# double-dice.net
KiCad netlist of a schematic drawn in EAGLE
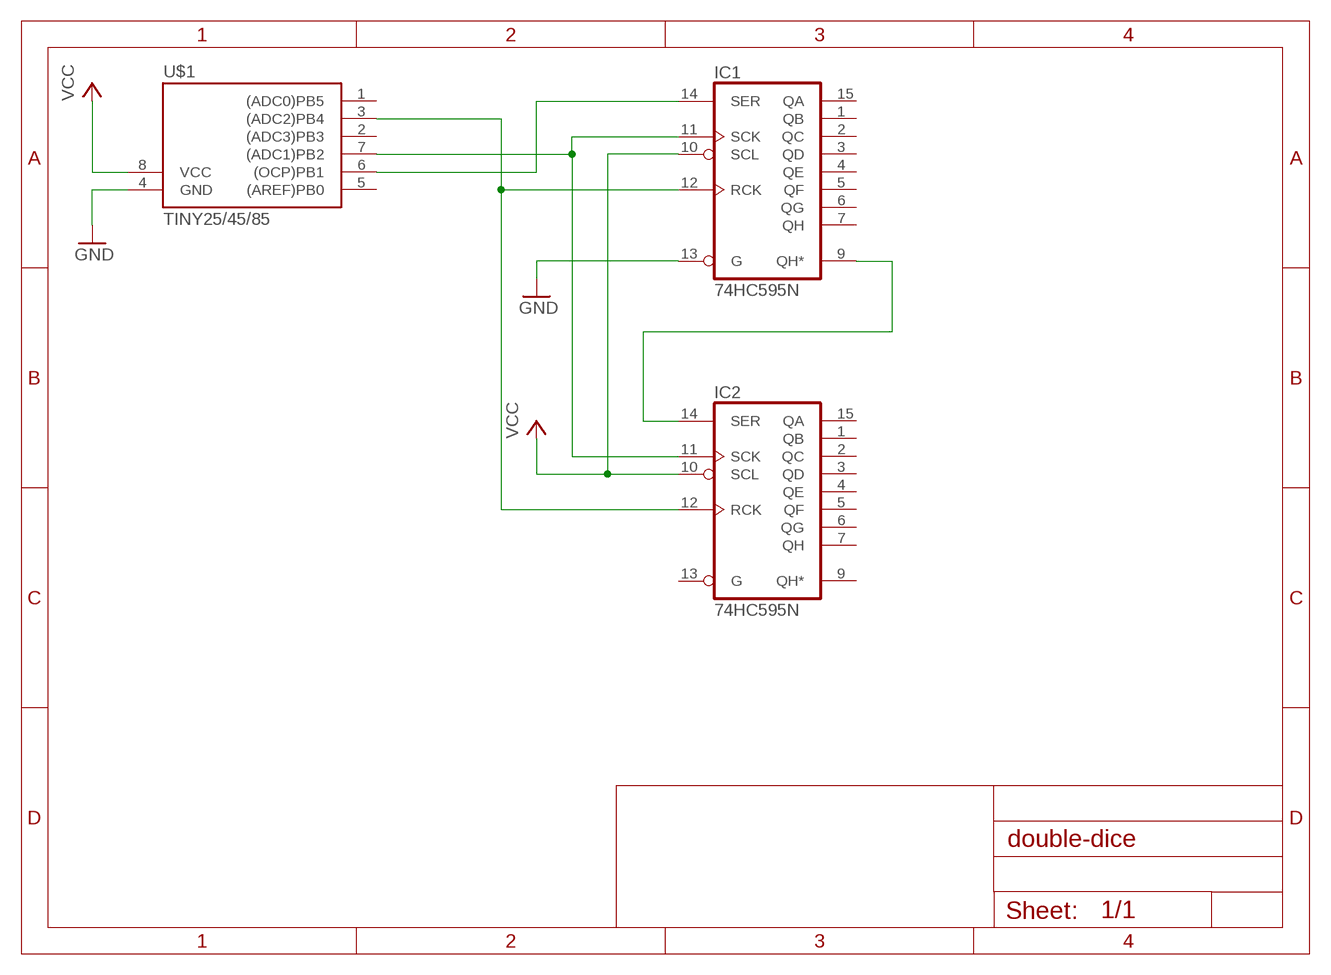
[diagram p0: schematic, sheet 1]

(export (version "E")
  (design (tool "Eeschema 10.0.6"))
  (components
    (comp (ref "IC1")
      (value "74HC595N")
      (footprint "eagle-import:DIL16")
      (libsource (lib "eagle-import") (part "74595NHC"))
    )
    (comp (ref "IC2")
      (value "74HC595N")
      (footprint "eagle-import:DIL16")
      (libsource (lib "eagle-import") (part "74595NHC"))
    )
    (comp (ref "U$1")
      (value "TINY25/45/85")
      (footprint "eagle-import:DIL08")
      (libsource (lib "eagle-import") (part "TINY25/45/85"))
    )
  )
  (nets
    (net (code "1") (name "GND") (class "Default")
      (node (ref "IC1") (pin "13") (pinfunction "G_13") (pintype "input"))
      (node (ref "U$1") (pin "4") (pinfunction "GND_4") (pintype "power_in"))
    )
    (net (code "2") (name "Net-(IC1A-QH*)") (class "Default")
      (node (ref "IC1") (pin "9") (pinfunction "QH*_9") (pintype "tri_state"))
      (node (ref "IC2") (pin "14") (pinfunction "SER_14") (pintype "input"))
    )
    (net (code "3") (name "Net-(IC1A-RCK)") (class "Default")
      (node (ref "IC1") (pin "12") (pinfunction "RCK_12") (pintype "input"))
      (node (ref "IC2") (pin "12") (pinfunction "RCK_12") (pintype "input"))
      (node (ref "U$1") (pin "3") (pinfunction "(ADC2)PB4_3") (pintype "bidirectional"))
    )
    (net (code "4") (name "Net-(IC1A-SCK)") (class "Default")
      (node (ref "IC1") (pin "11") (pinfunction "SCK_11") (pintype "input"))
      (node (ref "IC2") (pin "11") (pinfunction "SCK_11") (pintype "input"))
      (node (ref "U$1") (pin "7") (pinfunction "(ADC1)PB2_7") (pintype "bidirectional"))
    )
    (net (code "5") (name "Net-(IC1A-SER)") (class "Default")
      (node (ref "IC1") (pin "14") (pinfunction "SER_14") (pintype "input"))
      (node (ref "U$1") (pin "6") (pinfunction "(OCP)PB1_6") (pintype "bidirectional"))
    )
    (net (code "6") (name "VCC") (class "Default")
      (node (ref "IC1") (pin "10") (pinfunction "SCL_10") (pintype "input"))
      (node (ref "IC2") (pin "10") (pinfunction "SCL_10") (pintype "input"))
      (node (ref "U$1") (pin "8") (pinfunction "VCC_8") (pintype "power_in"))
    )
    (net (code "7") (name "unconnected-(IC1A-QA-Pad15)") (class "Default")
      (node (ref "IC1") (pin "15") (pinfunction "QA_15") (pintype "tri_state"))
    )
    (net (code "8") (name "unconnected-(IC1A-QB-Pad1)") (class "Default")
      (node (ref "IC1") (pin "1") (pinfunction "QB_1") (pintype "tri_state"))
    )
    (net (code "9") (name "unconnected-(IC1A-QC-Pad2)") (class "Default")
      (node (ref "IC1") (pin "2") (pinfunction "QC_2") (pintype "tri_state"))
    )
    (net (code "10") (name "unconnected-(IC1A-QD-Pad3)") (class "Default")
      (node (ref "IC1") (pin "3") (pinfunction "QD_3") (pintype "tri_state"))
    )
    (net (code "11") (name "unconnected-(IC1A-QE-Pad4)") (class "Default")
      (node (ref "IC1") (pin "4") (pinfunction "QE_4") (pintype "tri_state"))
    )
    (net (code "12") (name "unconnected-(IC1A-QF-Pad5)") (class "Default")
      (node (ref "IC1") (pin "5") (pinfunction "QF_5") (pintype "tri_state"))
    )
    (net (code "13") (name "unconnected-(IC1A-QG-Pad6)") (class "Default")
      (node (ref "IC1") (pin "6") (pinfunction "QG_6") (pintype "tri_state"))
    )
    (net (code "14") (name "unconnected-(IC1A-QH-Pad7)") (class "Default")
      (node (ref "IC1") (pin "7") (pinfunction "QH_7") (pintype "tri_state"))
    )
    (net (code "15") (name "unconnected-(IC2A-G-Pad13)") (class "Default")
      (node (ref "IC2") (pin "13") (pinfunction "G_13") (pintype "input"))
    )
    (net (code "16") (name "unconnected-(IC2A-QA-Pad15)") (class "Default")
      (node (ref "IC2") (pin "15") (pinfunction "QA_15") (pintype "tri_state"))
    )
    (net (code "17") (name "unconnected-(IC2A-QB-Pad1)") (class "Default")
      (node (ref "IC2") (pin "1") (pinfunction "QB_1") (pintype "tri_state"))
    )
    (net (code "18") (name "unconnected-(IC2A-QC-Pad2)") (class "Default")
      (node (ref "IC2") (pin "2") (pinfunction "QC_2") (pintype "tri_state"))
    )
    (net (code "19") (name "unconnected-(IC2A-QD-Pad3)") (class "Default")
      (node (ref "IC2") (pin "3") (pinfunction "QD_3") (pintype "tri_state"))
    )
    (net (code "20") (name "unconnected-(IC2A-QE-Pad4)") (class "Default")
      (node (ref "IC2") (pin "4") (pinfunction "QE_4") (pintype "tri_state"))
    )
    (net (code "21") (name "unconnected-(IC2A-QF-Pad5)") (class "Default")
      (node (ref "IC2") (pin "5") (pinfunction "QF_5") (pintype "tri_state"))
    )
    (net (code "22") (name "unconnected-(IC2A-QG-Pad6)") (class "Default")
      (node (ref "IC2") (pin "6") (pinfunction "QG_6") (pintype "tri_state"))
    )
    (net (code "23") (name "unconnected-(IC2A-QH*-Pad9)") (class "Default")
      (node (ref "IC2") (pin "9") (pinfunction "QH*_9") (pintype "tri_state"))
    )
    (net (code "24") (name "unconnected-(IC2A-QH-Pad7)") (class "Default")
      (node (ref "IC2") (pin "7") (pinfunction "QH_7") (pintype "tri_state"))
    )
    (net (code "25") (name "unconnected-(U$1-(ADC0)PB5-Pad1)") (class "Default")
      (node (ref "U$1") (pin "1") (pinfunction "(ADC0)PB5_1") (pintype "bidirectional"))
    )
    (net (code "26") (name "unconnected-(U$1-(ADC3)PB3-Pad2)") (class "Default")
      (node (ref "U$1") (pin "2") (pinfunction "(ADC3)PB3_2") (pintype "bidirectional"))
    )
    (net (code "27") (name "unconnected-(U$1-(AREF)PB0-Pad5)") (class "Default")
      (node (ref "U$1") (pin "5") (pinfunction "(AREF)PB0_5") (pintype "bidirectional"))
    )
  )
)
